# ccc-interface.net
KiCad netlist of a schematic drawn in EAGLE
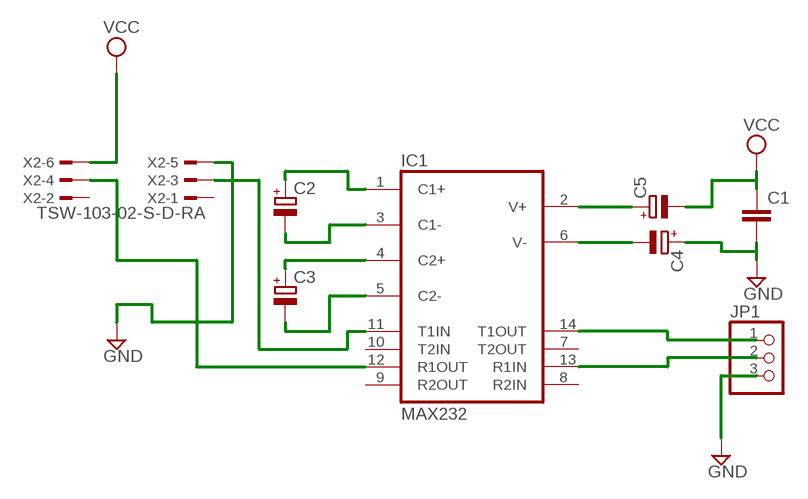
[diagram p0: schematic, sheet 1]

(export (version "E")
  (design (tool "Eeschema 10.0.6"))
  (components
    (comp (ref "C1")
      (value "C-EU050-024X044")
      (footprint "eagle-import:C050-024X044")
      (libsource (lib "eagle-import") (part "C-EU050-024X044"))
    )
    (comp (ref "C2")
      (value "CPOL-EUE1.8-4")
      (footprint "eagle-import:E1,8-4")
      (libsource (lib "eagle-import") (part "CPOL-EUE1.8-4"))
    )
    (comp (ref "C3")
      (value "CPOL-EUE1.8-4")
      (footprint "eagle-import:E1,8-4")
      (libsource (lib "eagle-import") (part "CPOL-EUE1.8-4"))
    )
    (comp (ref "C4")
      (value "CPOL-EUE1.8-4")
      (footprint "eagle-import:E1,8-4")
      (libsource (lib "eagle-import") (part "CPOL-EUE1.8-4"))
    )
    (comp (ref "C5")
      (value "CPOL-EUE1.8-4")
      (footprint "eagle-import:E1,8-4")
      (libsource (lib "eagle-import") (part "CPOL-EUE1.8-4"))
    )
    (comp (ref "IC1")
      (value "MAX232")
      (footprint "eagle-import:DIL16")
      (fields (field (name "MF") "MAXIM") (field (name "MPN") "MAX232ACPE+"))
      (libsource (lib "eagle-import") (part "MAX232"))
    )
    (comp (ref "JP1")
      (value "PINHD-1X3/90")
      (footprint "eagle-import:1X03_90")
      (libsource (lib "eagle-import") (part "PINHD-1X3/90"))
    )
    (comp (ref "X2")
      (value "TSW-103-02-S-D-RA")
      (footprint "eagle-import:TSW-103-02-S-D-RA")
      (libsource (lib "eagle-import") (part "TSW-103-02-S-D-RA"))
    )
  )
  (nets
    (net (code "1") (name "GND") (class "Default")
      (node (ref "C1") (pin "2") (pinfunction "2_2") (pintype "passive"))
      (node (ref "C4") (pin "+") (pinfunction "+_+") (pintype "passive"))
      (node (ref "JP1") (pin "3") (pinfunction "3_3") (pintype "passive"))
      (node (ref "X2") (pin "5") (pinfunction "1_5") (pintype "passive"))
    )
    (net (code "2") (name "Net-(IC1A-C1+)") (class "Default")
      (node (ref "C2") (pin "+") (pinfunction "+_+") (pintype "passive"))
      (node (ref "IC1") (pin "1") (pinfunction "C1+_1") (pintype "bidirectional"))
    )
    (net (code "3") (name "Net-(IC1A-C1-)") (class "Default")
      (node (ref "C2") (pin "-") (pinfunction "-_-") (pintype "passive"))
      (node (ref "IC1") (pin "3") (pinfunction "C1-_3") (pintype "bidirectional"))
    )
    (net (code "4") (name "Net-(IC1A-C2+)") (class "Default")
      (node (ref "C3") (pin "+") (pinfunction "+_+") (pintype "passive"))
      (node (ref "IC1") (pin "4") (pinfunction "C2+_4") (pintype "bidirectional"))
    )
    (net (code "5") (name "Net-(IC1A-C2-)") (class "Default")
      (node (ref "C3") (pin "-") (pinfunction "-_-") (pintype "passive"))
      (node (ref "IC1") (pin "5") (pinfunction "C2-_5") (pintype "bidirectional"))
    )
    (net (code "6") (name "Net-(IC1A-R1IN)") (class "Default")
      (node (ref "IC1") (pin "13") (pinfunction "R1IN_13") (pintype "input"))
      (node (ref "JP1") (pin "2") (pinfunction "2_2") (pintype "passive"))
    )
    (net (code "7") (name "Net-(IC1A-R1OUT)") (class "Default")
      (node (ref "IC1") (pin "12") (pinfunction "R1OUT_12") (pintype "output"))
      (node (ref "X2") (pin "4") (pinfunction "1_4") (pintype "passive"))
    )
    (net (code "8") (name "Net-(IC1A-T1IN)") (class "Default")
      (node (ref "IC1") (pin "11") (pinfunction "T1IN_11") (pintype "input"))
      (node (ref "X2") (pin "3") (pinfunction "1_3") (pintype "passive"))
    )
    (net (code "9") (name "Net-(IC1A-T1OUT)") (class "Default")
      (node (ref "IC1") (pin "14") (pinfunction "T1OUT_14") (pintype "output"))
      (node (ref "JP1") (pin "1") (pinfunction "1_1") (pintype "passive"))
    )
    (net (code "10") (name "Net-(IC1A-V+)") (class "Default")
      (node (ref "C5") (pin "+") (pinfunction "+_+") (pintype "passive"))
      (node (ref "IC1") (pin "2") (pinfunction "V+_2") (pintype "bidirectional"))
    )
    (net (code "11") (name "Net-(IC1A-V-)") (class "Default")
      (node (ref "C4") (pin "-") (pinfunction "-_-") (pintype "passive"))
      (node (ref "IC1") (pin "6") (pinfunction "V-_6") (pintype "bidirectional"))
    )
    (net (code "12") (name "VCC") (class "Default")
      (node (ref "C1") (pin "1") (pinfunction "1_1") (pintype "passive"))
      (node (ref "C5") (pin "-") (pinfunction "-_-") (pintype "passive"))
      (node (ref "X2") (pin "6") (pinfunction "1_6") (pintype "passive"))
    )
    (net (code "13") (name "unconnected-(IC1A-R2IN-Pad8)") (class "Default")
      (node (ref "IC1") (pin "8") (pinfunction "R2IN_8") (pintype "input"))
    )
    (net (code "14") (name "unconnected-(IC1A-R2OUT-Pad9)") (class "Default")
      (node (ref "IC1") (pin "9") (pinfunction "R2OUT_9") (pintype "output"))
    )
    (net (code "15") (name "unconnected-(IC1A-T2IN-Pad10)") (class "Default")
      (node (ref "IC1") (pin "10") (pinfunction "T2IN_10") (pintype "input"))
    )
    (net (code "16") (name "unconnected-(IC1A-T2OUT-Pad7)") (class "Default")
      (node (ref "IC1") (pin "7") (pinfunction "T2OUT_7") (pintype "output"))
    )
    (net (code "17") (name "unconnected-(X2-Pad1)") (class "Default")
      (node (ref "X2") (pin "1") (pinfunction "1_1") (pintype "passive"))
    )
    (net (code "18") (name "unconnected-(X2B-1-Pad2)") (class "Default")
      (node (ref "X2") (pin "2") (pinfunction "1_2") (pintype "passive"))
    )
  )
)
